# MyRollerShutter_nrf_1-3a.net
KiCad netlist of a schematic drawn in EAGLE
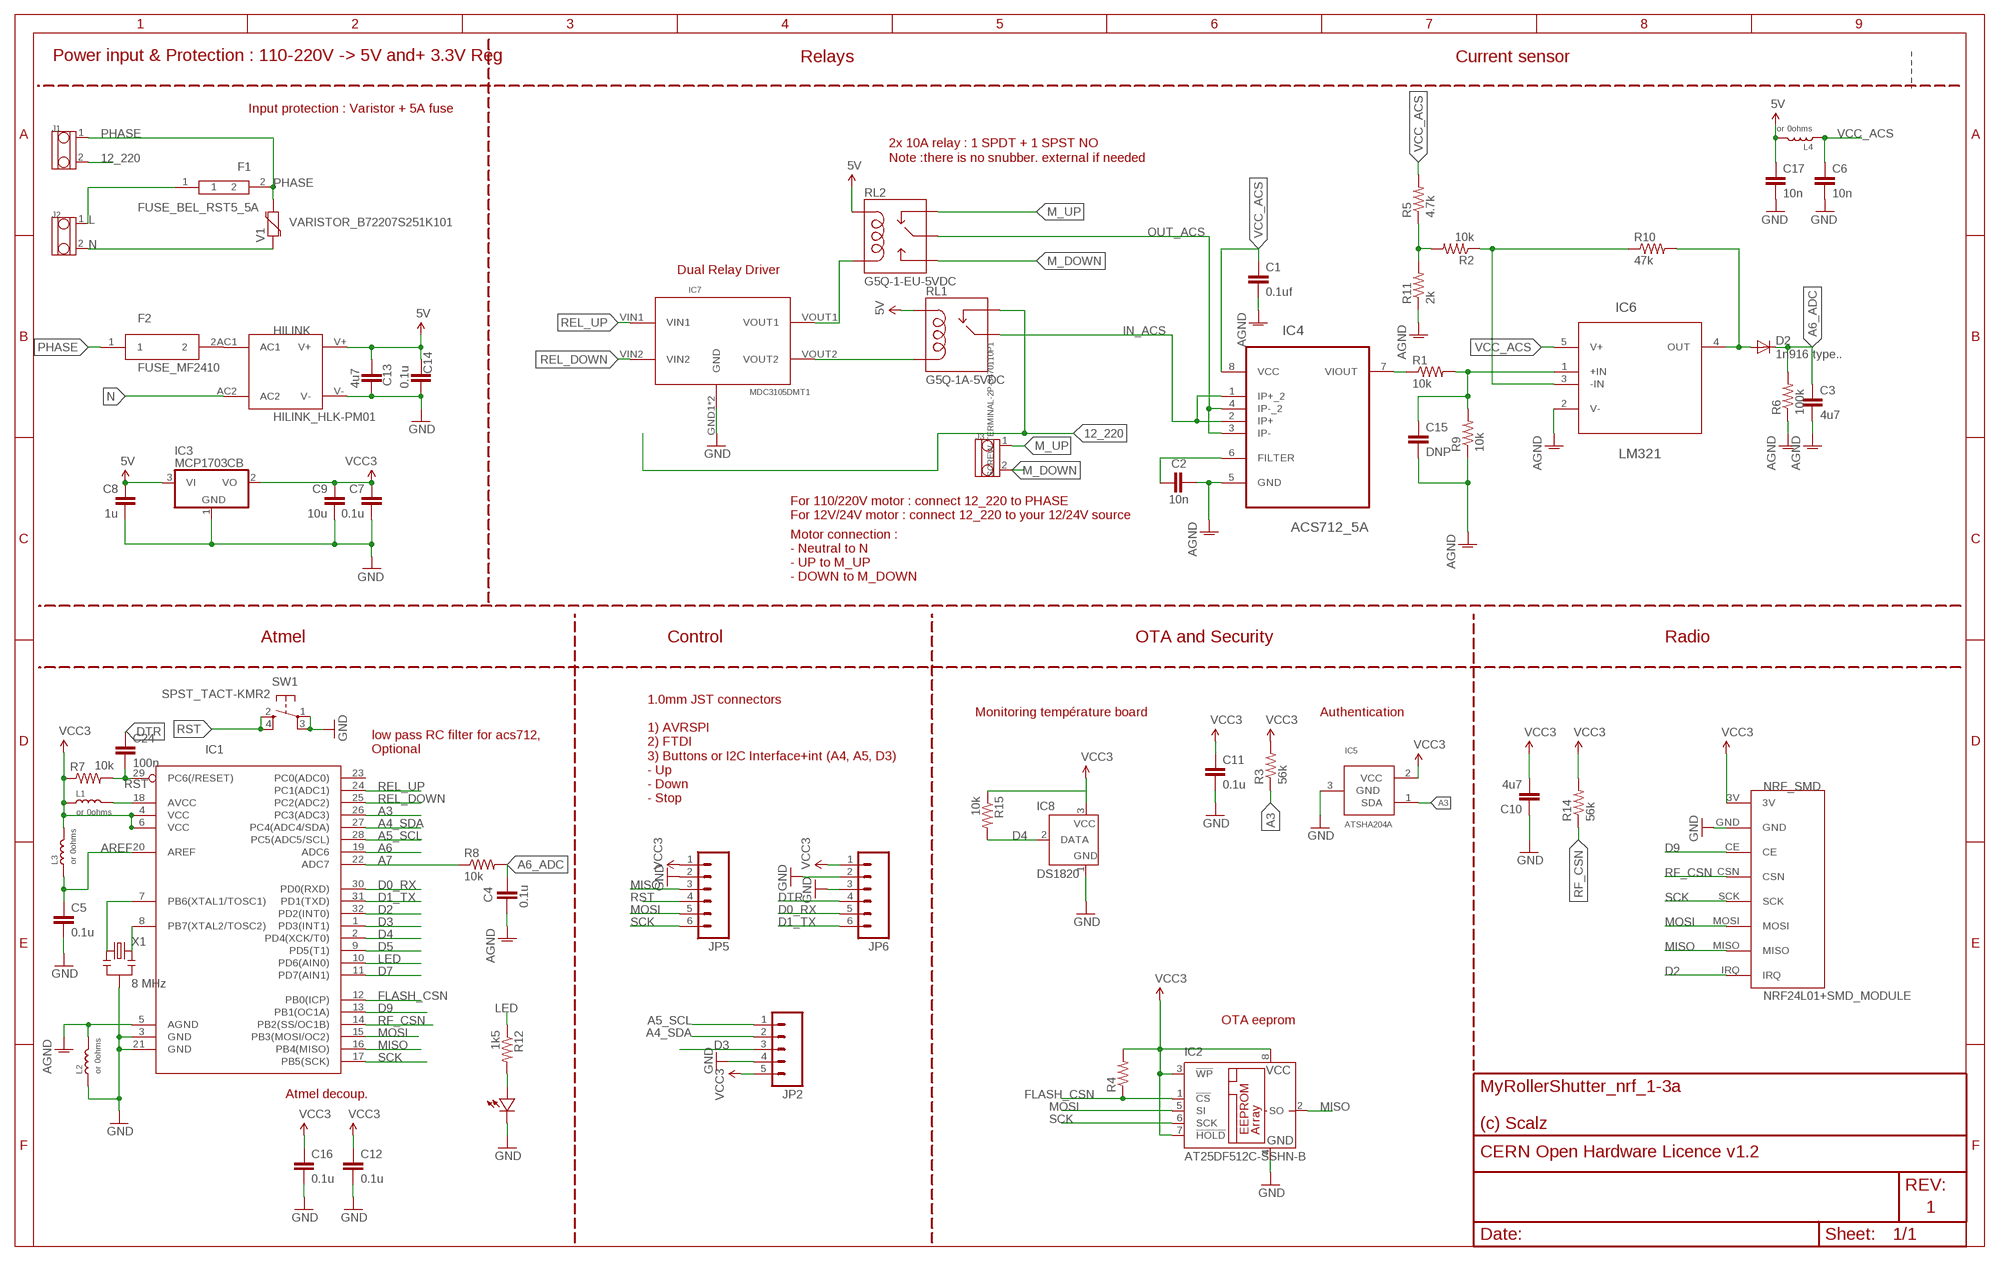
[diagram p0: schematic, sheet 1]

(export (version "E")
  (design (tool "Eeschema 10.0.6"))
  (components
    (comp (ref "C1")
      (value "0.1uf")
      (footprint "eagle-import:0805-CAP")
      (libsource (lib "eagle-import") (part "CAP0805-CAP"))
    )
    (comp (ref "C2")
      (value "10n")
      (footprint "eagle-import:0805-CAP")
      (libsource (lib "eagle-import") (part "CAP0805-CAP"))
    )
    (comp (ref "C3")
      (value "4u7")
      (footprint "eagle-import:0805-CAP")
      (libsource (lib "eagle-import") (part "CAP0805-CAP"))
    )
    (comp (ref "C4")
      (value "0.1u")
      (footprint "eagle-import:0805-CAP")
      (libsource (lib "eagle-import") (part "CAP0805-CAP"))
    )
    (comp (ref "C5")
      (value "0.1u")
      (footprint "eagle-import:0805-CAP")
      (libsource (lib "eagle-import") (part "CAP0805-CAP"))
    )
    (comp (ref "C6")
      (value "10n")
      (footprint "eagle-import:0805-CAP")
      (libsource (lib "eagle-import") (part "CAP0805-CAP"))
    )
    (comp (ref "C7")
      (value "0.1u")
      (footprint "eagle-import:0805-CAP")
      (libsource (lib "eagle-import") (part "CAP0805-CAP"))
    )
    (comp (ref "C8")
      (value "1u")
      (footprint "eagle-import:0805-CAP")
      (libsource (lib "eagle-import") (part "CAP0805-CAP"))
    )
    (comp (ref "C9")
      (value "10u")
      (footprint "eagle-import:0805-CAP")
      (libsource (lib "eagle-import") (part "CAP0805-CAP"))
    )
    (comp (ref "C10")
      (value "4u7")
      (footprint "eagle-import:0805-CAP")
      (libsource (lib "eagle-import") (part "CAP0805-CAP"))
    )
    (comp (ref "C11")
      (value "0.1u")
      (footprint "eagle-import:0805-CAP")
      (libsource (lib "eagle-import") (part "CAP0805-CAP"))
    )
    (comp (ref "C12")
      (value "0.1u")
      (footprint "eagle-import:0805-CAP")
      (libsource (lib "eagle-import") (part "CAP0805-CAP"))
    )
    (comp (ref "C13")
      (value "4u7")
      (footprint "eagle-import:0805-CAP")
      (libsource (lib "eagle-import") (part "CAP0805-CAP"))
    )
    (comp (ref "C14")
      (value "0.1u")
      (footprint "eagle-import:0805-CAP")
      (libsource (lib "eagle-import") (part "CAP0805-CAP"))
    )
    (comp (ref "C15")
      (value "DNP")
      (footprint "eagle-import:0805-CAP")
      (libsource (lib "eagle-import") (part "CAP0805-CAP"))
    )
    (comp (ref "C16")
      (value "0.1u")
      (footprint "eagle-import:0805-CAP")
      (libsource (lib "eagle-import") (part "CAP0805-CAP"))
    )
    (comp (ref "C17")
      (value "10n")
      (footprint "eagle-import:0805-CAP")
      (libsource (lib "eagle-import") (part "CAP0805-CAP"))
    )
    (comp (ref "C24")
      (value "100n")
      (footprint "eagle-import:0805-CAP")
      (libsource (lib "eagle-import") (part "CAP0805-CAP"))
    )
    (comp (ref "D1")
      (value "LED0805")
      (footprint "eagle-import:0805-LED")
      (libsource (lib "eagle-import") (part "LED0805"))
    )
    (comp (ref "D2")
      (value "1n916 type..")
      (footprint "eagle-import:SOD-323")
      (libsource (lib "eagle-import") (part "DIODESOD"))
    )
    (comp (ref "F1")
      (value "FUSE_BEL_RST5_5A")
      (footprint "eagle-import:FUSE_BEL_RST5_5A")
      (libsource (lib "eagle-import") (part "FUSE_BEL_RST5_5A"))
    )
    (comp (ref "F2")
      (value "FUSE_MF2410")
      (footprint "eagle-import:2410")
      (libsource (lib "eagle-import") (part "FUSE_MF2410"))
    )
    (comp (ref "HILINK")
      (value "HILINK_HLK-PM01")
      (footprint "eagle-import:HILINK_HLK-PM01")
      (libsource (lib "eagle-import") (part "HILINK_HLK-PM01"))
    )
    (comp (ref "IC1")
      (value "ATMega-328")
      (footprint "eagle-import:TQFP32-08")
      (libsource (lib "eagle-import") (part "ATMEGA168/328TQFP32"))
    )
    (comp (ref "IC2")
      (value "AT25DF512C-SSHN-B")
      (footprint "eagle-import:SO-08")
      (fields (field (name "MF") "MICROCHIP") (field (name "MPN") "25AA080/SN"))
      (libsource (lib "eagle-import") (part "25SNAA080"))
    )
    (comp (ref "IC3")
      (value "MCP1703CB")
      (footprint "eagle-import:SOT23")
      (libsource (lib "eagle-import") (part "MCP1703CB"))
    )
    (comp (ref "IC4")
      (value "ACS712_5A")
      (footprint "eagle-import:SOIC127P600X175-8N")
      (fields (field (name "MPN") "ACS712ELCTR-20A-T"))
      (libsource (lib "eagle-import") (part "ACS712ELCTR-20A-T"))
    )
    (comp (ref "IC5")
      (value "ATSHA204A")
      (footprint "eagle-import:SOT23")
      (libsource (lib "eagle-import") (part "ATSHA204A"))
    )
    (comp (ref "IC6")
      (value "LM321")
      (footprint "eagle-import:SOT95P285X120-5N")
      (fields (field (name "MPN") "LM321MF"))
      (libsource (lib "eagle-import") (part "LM321MF"))
    )
    (comp (ref "IC7")
      (value "MDC3105DMT1")
      (footprint "eagle-import:MDC3105DMT1")
      (libsource (lib "eagle-import") (part "MDC3105DMT1"))
    )
    (comp (ref "IC8")
      (value "DS1820")
      (footprint "eagle-import:TO92-")
      (libsource (lib "eagle-import") (part "DS1820"))
    )
    (comp (ref "J1")
      (value "SCREW-TERMINAL-2P-3470110P1")
      (footprint "eagle-import:2P-5.0")
      (libsource (lib "eagle-import") (part "SCREW-TERMINAL-2P-3470110P1"))
    )
    (comp (ref "J2")
      (value "SCREW-TERMINAL-2P-3470110P1")
      (footprint "eagle-import:2P-5.0")
      (libsource (lib "eagle-import") (part "SCREW-TERMINAL-2P-3470110P1"))
    )
    (comp (ref "J3")
      (value "SCREW-TERMINAL-2P-3470110P1")
      (footprint "eagle-import:2P-5.0")
      (libsource (lib "eagle-import") (part "SCREW-TERMINAL-2P-3470110P1"))
    )
    (comp (ref "JP2")
      (value "M05SMD")
      (footprint "eagle-import:1X05-1MM")
      (libsource (lib "eagle-import") (part "M05SMD"))
    )
    (comp (ref "JP5")
      (value "M06SMD-1MM")
      (footprint "eagle-import:1X06-1MM")
      (libsource (lib "eagle-import") (part "M06SMD-1MM"))
    )
    (comp (ref "JP6")
      (value "M06SMD-1MM")
      (footprint "eagle-import:1X06-1MM")
      (libsource (lib "eagle-import") (part "M06SMD-1MM"))
    )
    (comp (ref "L1")
      (value "or 0ohms")
      (footprint "eagle-import:L0805")
      (libsource (lib "eagle-import") (part "INDUCTOR/FERRITE-BEAD-0805"))
    )
    (comp (ref "L2")
      (value "or 0ohms")
      (footprint "eagle-import:L0805")
      (libsource (lib "eagle-import") (part "INDUCTOR/FERRITE-BEAD-0805"))
    )
    (comp (ref "L3")
      (value "or 0ohms")
      (footprint "eagle-import:L0805")
      (libsource (lib "eagle-import") (part "INDUCTOR/FERRITE-BEAD-0805"))
    )
    (comp (ref "L4")
      (value "or 0ohms")
      (footprint "eagle-import:L0805")
      (libsource (lib "eagle-import") (part "INDUCTOR/FERRITE-BEAD-0805"))
    )
    (comp (ref "NRF_SMD")
      (value "NRF24L01+SMD_MODULE")
      (footprint "eagle-import:NRF24L01+SMD_MODULE")
      (libsource (lib "eagle-import") (part "NRF24L01+SMD_MODULE"))
    )
    (comp (ref "R1")
      (value "10k")
      (footprint "eagle-import:0805-RES")
      (libsource (lib "eagle-import") (part "RESISTOR0805-RES"))
    )
    (comp (ref "R2")
      (value "10k")
      (footprint "eagle-import:0805-RES")
      (libsource (lib "eagle-import") (part "RESISTOR0805-RES"))
    )
    (comp (ref "R3")
      (value "56k")
      (footprint "eagle-import:0805-RES")
      (libsource (lib "eagle-import") (part "RESISTOR0805-RES"))
    )
    (comp (ref "R4")
      (value "RESISTOR0805-RES")
      (footprint "eagle-import:0805-RES")
      (libsource (lib "eagle-import") (part "RESISTOR0805-RES"))
    )
    (comp (ref "R5")
      (value "4.7k")
      (footprint "eagle-import:0805-RES")
      (libsource (lib "eagle-import") (part "RESISTOR0805-RES"))
    )
    (comp (ref "R6")
      (value "100k")
      (footprint "eagle-import:0805-RES")
      (libsource (lib "eagle-import") (part "RESISTOR0805-RES"))
    )
    (comp (ref "R7")
      (value "10k")
      (footprint "eagle-import:0805-RES")
      (libsource (lib "eagle-import") (part "RESISTOR0805-RES"))
    )
    (comp (ref "R8")
      (value "10k")
      (footprint "eagle-import:0805-RES")
      (libsource (lib "eagle-import") (part "RESISTOR0805-RES"))
    )
    (comp (ref "R9")
      (value "10k")
      (footprint "eagle-import:0805-RES")
      (libsource (lib "eagle-import") (part "RESISTOR0805-RES"))
    )
    (comp (ref "R10")
      (value "47k")
      (footprint "eagle-import:0805-RES")
      (libsource (lib "eagle-import") (part "RESISTOR0805-RES"))
    )
    (comp (ref "R11")
      (value "2k")
      (footprint "eagle-import:0805-RES")
      (libsource (lib "eagle-import") (part "RESISTOR0805-RES"))
    )
    (comp (ref "R12")
      (value "1k5")
      (footprint "eagle-import:0805-RES")
      (libsource (lib "eagle-import") (part "RESISTOR0805-RES"))
    )
    (comp (ref "R14")
      (value "56k")
      (footprint "eagle-import:0805-RES")
      (libsource (lib "eagle-import") (part "RESISTOR0805-RES"))
    )
    (comp (ref "R15")
      (value "10k")
      (footprint "eagle-import:0805-RES")
      (libsource (lib "eagle-import") (part "RESISTOR0805-RES"))
    )
    (comp (ref "RL1")
      (value "G5Q-1A-5VDC")
      (footprint "eagle-import:G5Q_SINGLE")
      (libsource (lib "eagle-import") (part "G5Q_SINGLE"))
    )
    (comp (ref "RL2")
      (value "G5Q-1-EU-5VDC")
      (footprint "eagle-import:RELAY-G5Q")
      (libsource (lib "eagle-import") (part "RELAYPTH"))
    )
    (comp (ref "SW1")
      (value "SPST_TACT-KMR2")
      (footprint "eagle-import:KMR2")
      (libsource (lib "eagle-import") (part "SPST_TACT-KMR2"))
    )
    (comp (ref "V1")
      (value "VARISTOR_B72207S251K101")
      (footprint "eagle-import:VARISTOR_B72207S251K101")
      (libsource (lib "eagle-import") (part "VARISTOR_B72207S251K101"))
    )
    (comp (ref "X1")
      (value "8 MHz")
      (footprint "eagle-import:RESONATOR-SMD")
      (libsource (lib "eagle-import") (part "RESONATORSMD"))
    )
  )
  (nets
    (net (code "1") (name "/A4_SDA") (class "Default")
      (node (ref "IC1") (pin "27") (pinfunction "PC4(ADC4/SDA)_27") (pintype "bidirectional"))
      (node (ref "JP2") (pin "2") (pinfunction "2_2") (pintype "passive"))
    )
    (net (code "2") (name "/A5_SCL") (class "Default")
      (node (ref "IC1") (pin "28") (pinfunction "PC5(ADC5/SCL)_28") (pintype "bidirectional"))
      (node (ref "JP2") (pin "1") (pinfunction "1_1") (pintype "passive"))
    )
    (net (code "3") (name "/A6") (class "Default")
      (node (ref "IC1") (pin "19") (pinfunction "ADC6_19") (pintype "bidirectional"))
    )
    (net (code "4") (name "/A7") (class "Default")
      (node (ref "IC1") (pin "22") (pinfunction "ADC7_22") (pintype "bidirectional"))
      (node (ref "R8") (pin "1") (pinfunction "1_1") (pintype "passive"))
    )
    (net (code "5") (name "/AREF") (class "Default")
      (node (ref "C5") (pin "1") (pinfunction "1_1") (pintype "passive"))
      (node (ref "IC1") (pin "20") (pinfunction "AREF_20") (pintype "bidirectional"))
      (node (ref "L3") (pin "1") (pinfunction "1_1") (pintype "passive"))
    )
    (net (code "6") (name "/D0_RX") (class "Default")
      (node (ref "IC1") (pin "30") (pinfunction "PD0(RXD)_30") (pintype "bidirectional"))
      (node (ref "JP6") (pin "5") (pinfunction "5_5") (pintype "passive"))
    )
    (net (code "7") (name "/D1_TX") (class "Default")
      (node (ref "IC1") (pin "31") (pinfunction "PD1(TXD)_31") (pintype "bidirectional"))
      (node (ref "JP6") (pin "6") (pinfunction "6_6") (pintype "passive"))
    )
    (net (code "8") (name "/D2") (class "Default")
      (node (ref "IC1") (pin "32") (pinfunction "PD2(INT0)_32") (pintype "bidirectional"))
      (node (ref "NRF_SMD") (pin "IRQ") (pinfunction "IRQ_IRQ") (pintype "bidirectional"))
    )
    (net (code "9") (name "/D3") (class "Default")
      (node (ref "IC1") (pin "1") (pinfunction "PD3(INT1)_1") (pintype "bidirectional"))
      (node (ref "JP2") (pin "3") (pinfunction "3_3") (pintype "passive"))
    )
    (net (code "10") (name "/D4") (class "Default")
      (node (ref "IC1") (pin "2") (pinfunction "PD4(XCK/T0)_2") (pintype "bidirectional"))
      (node (ref "IC8") (pin "2") (pinfunction "DATA_2") (pintype "input"))
      (node (ref "R15") (pin "2") (pinfunction "2_2") (pintype "passive"))
    )
    (net (code "11") (name "/D5") (class "Default")
      (node (ref "IC1") (pin "9") (pinfunction "PD5(T1)_9") (pintype "bidirectional"))
    )
    (net (code "12") (name "/D7") (class "Default")
      (node (ref "IC1") (pin "11") (pinfunction "PD7(AIN1)_11") (pintype "bidirectional"))
    )
    (net (code "13") (name "/D9") (class "Default")
      (node (ref "IC1") (pin "13") (pinfunction "PB1(OC1A)_13") (pintype "bidirectional"))
      (node (ref "NRF_SMD") (pin "CE") (pinfunction "CE_CE") (pintype "bidirectional"))
    )
    (net (code "14") (name "/FLASH_CSN") (class "Default")
      (node (ref "IC1") (pin "12") (pinfunction "PB0(ICP)_12") (pintype "bidirectional"))
      (node (ref "IC2") (pin "1") (pinfunction "~{CS}_1") (pintype "input"))
      (node (ref "R4") (pin "1") (pinfunction "1_1") (pintype "passive"))
    )
    (net (code "15") (name "/IN_ACS") (class "Default")
      (node (ref "IC4") (pin "1") (pinfunction "IP+_2_1") (pintype "input"))
      (node (ref "IC4") (pin "2") (pinfunction "IP+_2") (pintype "input"))
      (node (ref "RL1") (pin "2") (pinfunction "MAIN_2") (pintype "bidirectional"))
    )
    (net (code "16") (name "/L") (class "Default")
      (node (ref "F1") (pin "1") (pinfunction "1_1") (pintype "bidirectional"))
      (node (ref "J2") (pin "1") (pinfunction "1_1") (pintype "bidirectional"))
    )
    (net (code "17") (name "/LED") (class "Default")
      (node (ref "IC1") (pin "10") (pinfunction "PD6(AIN0)_10") (pintype "bidirectional"))
      (node (ref "R12") (pin "1") (pinfunction "1_1") (pintype "passive"))
    )
    (net (code "18") (name "/MISO") (class "Default")
      (node (ref "IC1") (pin "16") (pinfunction "PB4(MISO)_16") (pintype "bidirectional"))
      (node (ref "IC2") (pin "2") (pinfunction "SO_2") (pintype "bidirectional"))
      (node (ref "JP5") (pin "3") (pinfunction "3_3") (pintype "passive"))
      (node (ref "NRF_SMD") (pin "MISO") (pinfunction "MISO_MISO") (pintype "bidirectional"))
    )
    (net (code "19") (name "/MOSI") (class "Default")
      (node (ref "IC1") (pin "15") (pinfunction "PB3(MOSI/OC2)_15") (pintype "bidirectional"))
      (node (ref "IC2") (pin "5") (pinfunction "SI_5") (pintype "input"))
      (node (ref "JP5") (pin "5") (pinfunction "5_5") (pintype "passive"))
      (node (ref "NRF_SMD") (pin "MOSI") (pinfunction "MOSI_MOSI") (pintype "bidirectional"))
    )
    (net (code "20") (name "/OUT_ACS") (class "Default")
      (node (ref "IC4") (pin "3") (pinfunction "IP-_3") (pintype "input"))
      (node (ref "IC4") (pin "4") (pinfunction "IP-_2_4") (pintype "input"))
      (node (ref "RL2") (pin "2") (pinfunction "MAIN_2") (pintype "bidirectional"))
    )
    (net (code "21") (name "/SCK") (class "Default")
      (node (ref "IC1") (pin "17") (pinfunction "PB5(SCK)_17") (pintype "bidirectional"))
      (node (ref "IC2") (pin "6") (pinfunction "SCK_6") (pintype "input"))
      (node (ref "JP5") (pin "6") (pinfunction "6_6") (pintype "passive"))
      (node (ref "NRF_SMD") (pin "SCK") (pinfunction "SCK_SCK") (pintype "bidirectional"))
    )
    (net (code "22") (name "5V") (class "Default")
      (node (ref "C13") (pin "1") (pinfunction "1_1") (pintype "passive"))
      (node (ref "C14") (pin "1") (pinfunction "1_1") (pintype "passive"))
      (node (ref "C17") (pin "1") (pinfunction "1_1") (pintype "passive"))
      (node (ref "C8") (pin "1") (pinfunction "1_1") (pintype "passive"))
      (node (ref "HILINK") (pin "V+") (pinfunction "V+_V+") (pintype "bidirectional"))
      (node (ref "IC3") (pin "3") (pinfunction "VI_3") (pintype "input"))
      (node (ref "L4") (pin "2") (pinfunction "2_2") (pintype "passive"))
      (node (ref "RL1") (pin "1") (pinfunction "COIL1_1") (pintype "bidirectional"))
      (node (ref "RL2") (pin "5") (pinfunction "COIL1_5") (pintype "bidirectional"))
    )
    (net (code "23") (name "12_220") (class "Default")
      (node (ref "J1") (pin "2") (pinfunction "2_2") (pintype "bidirectional"))
      (node (ref "RL1") (pin "3") (pinfunction "NC_3") (pintype "bidirectional"))
    )
    (net (code "24") (name "A3") (class "Default")
      (node (ref "IC1") (pin "26") (pinfunction "PC3(ADC3)_26") (pintype "bidirectional"))
      (node (ref "IC5") (pin "1") (pinfunction "SDA_1") (pintype "bidirectional"))
      (node (ref "R3") (pin "1") (pinfunction "1_1") (pintype "passive"))
    )
    (net (code "25") (name "A6_ADC") (class "Default")
      (node (ref "C3") (pin "1") (pinfunction "1_1") (pintype "passive"))
      (node (ref "C4") (pin "2") (pinfunction "2_2") (pintype "passive"))
      (node (ref "D2") (pin "1") (pinfunction "C_1") (pintype "passive"))
      (node (ref "R6") (pin "2") (pinfunction "2_2") (pintype "passive"))
      (node (ref "R8") (pin "2") (pinfunction "2_2") (pintype "passive"))
    )
    (net (code "26") (name "AGND") (class "Default")
      (node (ref "C1") (pin "2") (pinfunction "2_2") (pintype "passive"))
      (node (ref "C15") (pin "2") (pinfunction "2_2") (pintype "passive"))
      (node (ref "C2") (pin "2") (pinfunction "2_2") (pintype "passive"))
      (node (ref "C3") (pin "2") (pinfunction "2_2") (pintype "passive"))
      (node (ref "C4") (pin "1") (pinfunction "1_1") (pintype "passive"))
      (node (ref "IC1") (pin "5") (pinfunction "AGND_5") (pintype "bidirectional"))
      (node (ref "IC4") (pin "5") (pinfunction "GND_5") (pintype "passive"))
      (node (ref "IC6") (pin "2") (pinfunction "V-_2") (pintype "power_in"))
      (node (ref "L2") (pin "2") (pinfunction "2_2") (pintype "passive"))
      (node (ref "R11") (pin "1") (pinfunction "1_1") (pintype "passive"))
      (node (ref "R6") (pin "1") (pinfunction "1_1") (pintype "passive"))
      (node (ref "R9") (pin "1") (pinfunction "1_1") (pintype "passive"))
    )
    (net (code "27") (name "DTR") (class "Default")
      (node (ref "C24") (pin "1") (pinfunction "1_1") (pintype "passive"))
      (node (ref "JP6") (pin "4") (pinfunction "4_4") (pintype "passive"))
    )
    (net (code "28") (name "GND") (class "Default")
      (node (ref "C10") (pin "1") (pinfunction "1_1") (pintype "passive"))
      (node (ref "C11") (pin "2") (pinfunction "2_2") (pintype "passive"))
      (node (ref "C12") (pin "2") (pinfunction "2_2") (pintype "passive"))
      (node (ref "C13") (pin "2") (pinfunction "2_2") (pintype "passive"))
      (node (ref "C14") (pin "2") (pinfunction "2_2") (pintype "passive"))
      (node (ref "C16") (pin "2") (pinfunction "2_2") (pintype "passive"))
      (node (ref "C17") (pin "2") (pinfunction "2_2") (pintype "passive"))
      (node (ref "C5") (pin "2") (pinfunction "2_2") (pintype "passive"))
      (node (ref "C6") (pin "2") (pinfunction "2_2") (pintype "passive"))
      (node (ref "C7") (pin "2") (pinfunction "2_2") (pintype "passive"))
      (node (ref "C8") (pin "2") (pinfunction "2_2") (pintype "passive"))
      (node (ref "C9") (pin "2") (pinfunction "2_2") (pintype "passive"))
      (node (ref "D1") (pin "MINUS") (pinfunction "MINUS_MINUS") (pintype "passive"))
      (node (ref "HILINK") (pin "V-") (pinfunction "V-_V-") (pintype "bidirectional"))
      (node (ref "IC1") (pin "21") (pinfunction "GND_21") (pintype "bidirectional"))
      (node (ref "IC1") (pin "3") (pinfunction "GND_3") (pintype "bidirectional"))
      (node (ref "IC2") (pin "4") (pinfunction "GND_4") (pintype "power_in"))
      (node (ref "IC3") (pin "1") (pinfunction "GND_1") (pintype "passive"))
      (node (ref "IC5") (pin "3") (pinfunction "GND_3") (pintype "bidirectional"))
      (node (ref "IC7") (pin "GND1") (pinfunction "GND_GND1") (pintype "bidirectional"))
      (node (ref "IC7") (pin "GND2") (pinfunction "GND_GND2") (pintype "bidirectional"))
      (node (ref "IC8") (pin "1") (pinfunction "GND_1") (pintype "passive"))
      (node (ref "JP2") (pin "4") (pinfunction "4_4") (pintype "passive"))
      (node (ref "JP5") (pin "2") (pinfunction "2_2") (pintype "passive"))
      (node (ref "JP6") (pin "2") (pinfunction "2_2") (pintype "passive"))
      (node (ref "JP6") (pin "3") (pinfunction "3_3") (pintype "passive"))
      (node (ref "L2") (pin "1") (pinfunction "1_1") (pintype "passive"))
      (node (ref "NRF_SMD") (pin "GND") (pinfunction "GND_GND") (pintype "bidirectional"))
      (node (ref "SW1") (pin "1") (pinfunction "P_1") (pintype "passive"))
      (node (ref "SW1") (pin "3") (pinfunction "P1_3") (pintype "passive"))
      (node (ref "X1") (pin "2") (pinfunction "2_2") (pintype "passive"))
    )
    (net (code "29") (name "M_DOWN") (class "Default")
      (node (ref "J3") (pin "2") (pinfunction "2_2") (pintype "bidirectional"))
      (node (ref "RL2") (pin "3") (pinfunction "NO_3") (pintype "bidirectional"))
    )
    (net (code "30") (name "M_UP") (class "Default")
      (node (ref "J3") (pin "1") (pinfunction "1_1") (pintype "bidirectional"))
      (node (ref "RL2") (pin "4") (pinfunction "NC_4") (pintype "bidirectional"))
    )
    (net (code "31") (name "N") (class "Default")
      (node (ref "HILINK") (pin "AC2") (pinfunction "AC2_AC2") (pintype "bidirectional"))
      (node (ref "J2") (pin "2") (pinfunction "2_2") (pintype "bidirectional"))
      (node (ref "V1") (pin "1") (pinfunction "1_1") (pintype "passive"))
    )
    (net (code "32") (name "Net-(D1-PadPLUS)") (class "Default")
      (node (ref "D1") (pin "PLUS") (pinfunction "PLUS_PLUS") (pintype "passive"))
      (node (ref "R12") (pin "2") (pinfunction "2_2") (pintype "passive"))
    )
    (net (code "33") (name "Net-(D2-A)") (class "Default")
      (node (ref "D2") (pin "2") (pinfunction "A_2") (pintype "passive"))
      (node (ref "IC6") (pin "4") (pinfunction "OUT_4") (pintype "output"))
      (node (ref "R10") (pin "2") (pinfunction "2_2") (pintype "passive"))
    )
    (net (code "34") (name "Net-(F2-Pad2)") (class "Default")
      (node (ref "F2") (pin "2") (pinfunction "2_2") (pintype "bidirectional"))
      (node (ref "HILINK") (pin "AC1") (pinfunction "AC1_AC1") (pintype "bidirectional"))
    )
    (net (code "35") (name "Net-(IC1-AVCC)") (class "Default")
      (node (ref "IC1") (pin "18") (pinfunction "AVCC_18") (pintype "bidirectional"))
      (node (ref "L1") (pin "2") (pinfunction "2_2") (pintype "passive"))
    )
    (net (code "36") (name "Net-(IC1-PB6(XTAL1{slash}TOSC1))") (class "Default")
      (node (ref "IC1") (pin "7") (pinfunction "PB6(XTAL1/TOSC1)_7") (pintype "bidirectional"))
      (node (ref "X1") (pin "1") (pinfunction "1_1") (pintype "passive"))
    )
    (net (code "37") (name "Net-(IC1-PB7(XTAL2{slash}TOSC2))") (class "Default")
      (node (ref "IC1") (pin "8") (pinfunction "PB7(XTAL2/TOSC2)_8") (pintype "bidirectional"))
      (node (ref "X1") (pin "3") (pinfunction "3_3") (pintype "passive"))
    )
    (net (code "38") (name "Net-(IC4-FILTER)") (class "Default")
      (node (ref "C2") (pin "1") (pinfunction "1_1") (pintype "passive"))
      (node (ref "IC4") (pin "6") (pinfunction "FILTER_6") (pintype "input"))
    )
    (net (code "39") (name "Net-(IC4-VIOUT)") (class "Default")
      (node (ref "IC4") (pin "7") (pinfunction "VIOUT_7") (pintype "output"))
      (node (ref "R1") (pin "1") (pinfunction "1_1") (pintype "passive"))
    )
    (net (code "40") (name "Net-(IC6-+IN)") (class "Default")
      (node (ref "C15") (pin "1") (pinfunction "1_1") (pintype "passive"))
      (node (ref "IC6") (pin "1") (pinfunction "+IN_1") (pintype "input"))
      (node (ref "R1") (pin "2") (pinfunction "2_2") (pintype "passive"))
      (node (ref "R9") (pin "2") (pinfunction "2_2") (pintype "passive"))
    )
    (net (code "41") (name "Net-(IC6--IN)") (class "Default")
      (node (ref "IC6") (pin "3") (pinfunction "-IN_3") (pintype "input"))
      (node (ref "R10") (pin "1") (pinfunction "1_1") (pintype "passive"))
      (node (ref "R2") (pin "1") (pinfunction "1_1") (pintype "passive"))
    )
    (net (code "42") (name "Net-(R11-Pad2)") (class "Default")
      (node (ref "R11") (pin "2") (pinfunction "2_2") (pintype "passive"))
      (node (ref "R2") (pin "2") (pinfunction "2_2") (pintype "passive"))
      (node (ref "R5") (pin "1") (pinfunction "1_1") (pintype "passive"))
    )
    (net (code "43") (name "Net-(RL1-COIL2)") (class "Default")
      (node (ref "IC7") (pin "VOUT2") (pinfunction "VOUT2_VOUT2") (pintype "bidirectional"))
      (node (ref "RL1") (pin "5") (pinfunction "COIL2_5") (pintype "bidirectional"))
    )
    (net (code "44") (name "Net-(RL2-COIL2)") (class "Default")
      (node (ref "IC7") (pin "VOUT1") (pinfunction "VOUT1_VOUT1") (pintype "bidirectional"))
      (node (ref "RL2") (pin "1") (pinfunction "COIL2_1") (pintype "bidirectional"))
    )
    (net (code "45") (name "PHASE") (class "Default")
      (node (ref "F1") (pin "2") (pinfunction "2_2") (pintype "bidirectional"))
      (node (ref "F2") (pin "1") (pinfunction "1_1") (pintype "bidirectional"))
      (node (ref "J1") (pin "1") (pinfunction "1_1") (pintype "bidirectional"))
      (node (ref "V1") (pin "2") (pinfunction "2_2") (pintype "passive"))
    )
    (net (code "46") (name "REL_DOWN") (class "Default")
      (node (ref "IC1") (pin "25") (pinfunction "PC2(ADC2)_25") (pintype "bidirectional"))
      (node (ref "IC7") (pin "VIN2") (pinfunction "VIN2_VIN2") (pintype "bidirectional"))
    )
    (net (code "47") (name "REL_UP") (class "Default")
      (node (ref "IC1") (pin "24") (pinfunction "PC1(ADC1)_24") (pintype "bidirectional"))
      (node (ref "IC7") (pin "VIN1") (pinfunction "VIN1_VIN1") (pintype "bidirectional"))
    )
    (net (code "48") (name "RF_CSN") (class "Default")
      (node (ref "IC1") (pin "14") (pinfunction "PB2(SS/OC1B)_14") (pintype "bidirectional"))
      (node (ref "NRF_SMD") (pin "CSN") (pinfunction "CSN_CSN") (pintype "bidirectional"))
      (node (ref "R14") (pin "1") (pinfunction "1_1") (pintype "passive"))
    )
    (net (code "49") (name "RST") (class "Default")
      (node (ref "C24") (pin "2") (pinfunction "2_2") (pintype "passive"))
      (node (ref "IC1") (pin "29") (pinfunction "PC6(/RESET)_29") (pintype "bidirectional"))
      (node (ref "JP5") (pin "4") (pinfunction "4_4") (pintype "passive"))
      (node (ref "R7") (pin "2") (pinfunction "2_2") (pintype "passive"))
      (node (ref "SW1") (pin "2") (pinfunction "S_2") (pintype "passive"))
      (node (ref "SW1") (pin "4") (pinfunction "S1_4") (pintype "passive"))
    )
    (net (code "50") (name "VCC3") (class "Default")
      (node (ref "C10") (pin "2") (pinfunction "2_2") (pintype "passive"))
      (node (ref "C11") (pin "1") (pinfunction "1_1") (pintype "passive"))
      (node (ref "C12") (pin "1") (pinfunction "1_1") (pintype "passive"))
      (node (ref "C16") (pin "1") (pinfunction "1_1") (pintype "passive"))
      (node (ref "C7") (pin "1") (pinfunction "1_1") (pintype "passive"))
      (node (ref "C9") (pin "1") (pinfunction "1_1") (pintype "passive"))
      (node (ref "IC1") (pin "4") (pinfunction "VCC_4") (pintype "bidirectional"))
      (node (ref "IC1") (pin "6") (pinfunction "VCC_6") (pintype "bidirectional"))
      (node (ref "IC2") (pin "3") (pinfunction "~{WP}_3") (pintype "input"))
      (node (ref "IC2") (pin "7") (pinfunction "~{HOLD}_7") (pintype "input"))
      (node (ref "IC2") (pin "8") (pinfunction "VCC_8") (pintype "power_in"))
      (node (ref "IC3") (pin "2") (pinfunction "VO_2") (pintype "passive"))
      (node (ref "IC5") (pin "2") (pinfunction "VCC_2") (pintype "bidirectional"))
      (node (ref "IC8") (pin "3") (pinfunction "VCC_3") (pintype "passive"))
      (node (ref "JP2") (pin "5") (pinfunction "5_5") (pintype "passive"))
      (node (ref "JP5") (pin "1") (pinfunction "1_1") (pintype "passive"))
      (node (ref "JP6") (pin "1") (pinfunction "1_1") (pintype "passive"))
      (node (ref "L1") (pin "1") (pinfunction "1_1") (pintype "passive"))
      (node (ref "L3") (pin "2") (pinfunction "2_2") (pintype "passive"))
      (node (ref "NRF_SMD") (pin "3V") (pinfunction "3V_3V") (pintype "bidirectional"))
      (node (ref "R14") (pin "2") (pinfunction "2_2") (pintype "passive"))
      (node (ref "R15") (pin "1") (pinfunction "1_1") (pintype "passive"))
      (node (ref "R3") (pin "2") (pinfunction "2_2") (pintype "passive"))
      (node (ref "R4") (pin "2") (pinfunction "2_2") (pintype "passive"))
      (node (ref "R7") (pin "1") (pinfunction "1_1") (pintype "passive"))
    )
    (net (code "51") (name "VCC_ACS") (class "Default")
      (node (ref "C1") (pin "1") (pinfunction "1_1") (pintype "passive"))
      (node (ref "C6") (pin "1") (pinfunction "1_1") (pintype "passive"))
      (node (ref "IC4") (pin "8") (pinfunction "VCC_8") (pintype "power_in"))
      (node (ref "IC6") (pin "5") (pinfunction "V+_5") (pintype "power_in"))
      (node (ref "L4") (pin "1") (pinfunction "1_1") (pintype "passive"))
      (node (ref "R5") (pin "2") (pinfunction "2_2") (pintype "passive"))
    )
    (net (code "52") (name "unconnected-(IC1-PC0(ADC0)-Pad23)") (class "Default")
      (node (ref "IC1") (pin "23") (pinfunction "PC0(ADC0)_23") (pintype "bidirectional"))
    )
  )
)
